# mw_itb_full_v1_7_2.net
KiCad netlist of a schematic drawn in EAGLE
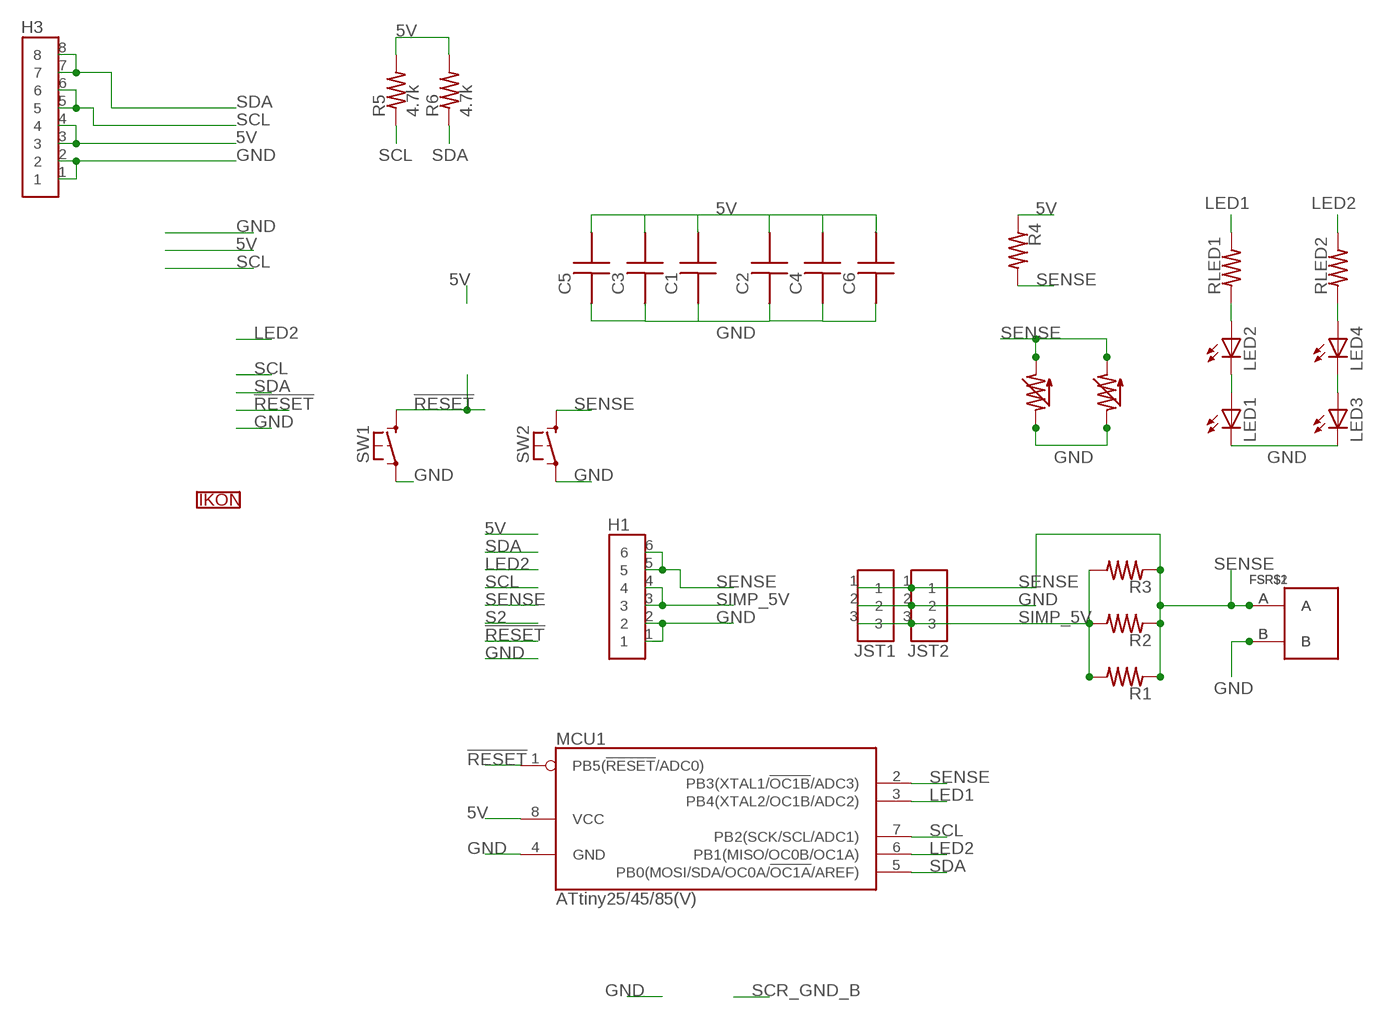
[diagram p0: schematic, sheet 1]

(export (version "E")
  (design (tool "Eeschema 10.0.6"))
  (components
    (comp (ref "C1")
      (value "CAPACITOR1206")
      (footprint "eagle-import:1206_YAGEO")
      (libsource (lib "eagle-import") (part "CAPACITOR1206"))
    )
    (comp (ref "C2")
      (value "CAPACITOR1206")
      (footprint "eagle-import:1206_YAGEO")
      (libsource (lib "eagle-import") (part "CAPACITOR1206"))
    )
    (comp (ref "C3")
      (value "CAPACITOR0805")
      (footprint "eagle-import:0805_YAGEO")
      (libsource (lib "eagle-import") (part "CAPACITOR0805"))
    )
    (comp (ref "C4")
      (value "CAPACITOR0805")
      (footprint "eagle-import:0805_YAGEO")
      (libsource (lib "eagle-import") (part "CAPACITOR0805"))
    )
    (comp (ref "C5")
      (value "CAPACITOR0603")
      (footprint "eagle-import:0603_YAGEO")
      (libsource (lib "eagle-import") (part "CAPACITOR0603"))
    )
    (comp (ref "C6")
      (value "CAPACITOR0603")
      (footprint "eagle-import:0603_YAGEO")
      (libsource (lib "eagle-import") (part "CAPACITOR0603"))
    )
    (comp (ref "FSR$1")
      (value "FSR_PAD88X44_P2B")
      (footprint "eagle-import:FSR_PAD_88X44_P2B")
      (libsource (lib "eagle-import") (part "FSR_PAD88X44_P2B"))
    )
    (comp (ref "FSR$2")
      (value "FSR_PAD88X44_P2B")
      (footprint "eagle-import:FSR_PAD_88X44_P2B")
      (libsource (lib "eagle-import") (part "FSR_PAD88X44_P2B"))
    )
    (comp (ref "H1")
      (value "HEADER_6P-0.1\"_2X3-SMD-SULLINS")
      (footprint "eagle-import:HEADER-0.1__2X3-SMD-SULLINS")
      (libsource (lib "eagle-import") (part "HEADER_6P-0.1{dblquote}_2X3-SMD-SULLINS"))
    )
    (comp (ref "H3")
      (value "HEADER_8P-0.1\"_2X4-SMD-SULLINS")
      (footprint "eagle-import:HEADER-0.1__2X4-SMD-SULLINS")
      (libsource (lib "eagle-import") (part "HEADER_8P-0.1{dblquote}_2X4-SMD-SULLINS"))
    )
    (comp (ref "JST1")
      (value "JST-3-PH-SMD-TOP")
      (footprint "eagle-import:JST_PH_SMD_3_TOP")
      (libsource (lib "eagle-import") (part "JST-3-PH-SMD-TOP"))
    )
    (comp (ref "JST2")
      (value "JST-3-PH-SMD-TOP")
      (footprint "eagle-import:JST_PH_SMD_3_TOP")
      (libsource (lib "eagle-import") (part "JST-3-PH-SMD-TOP"))
    )
    (comp (ref "LED1")
      (value "LED-ZBEND_RM")
      (footprint "eagle-import:Z-BEND_RM")
      (libsource (lib "eagle-import") (part "LED-ZBEND_RM"))
    )
    (comp (ref "LED2")
      (value "LED-ZBEND_RM")
      (footprint "eagle-import:Z-BEND_RM")
      (libsource (lib "eagle-import") (part "LED-ZBEND_RM"))
    )
    (comp (ref "LED3")
      (value "LED-ZBEND_RM")
      (footprint "eagle-import:Z-BEND_RM")
      (libsource (lib "eagle-import") (part "LED-ZBEND_RM"))
    )
    (comp (ref "LED4")
      (value "LED-ZBEND_RM")
      (footprint "eagle-import:Z-BEND_RM")
      (libsource (lib "eagle-import") (part "LED-ZBEND_RM"))
    )
    (comp (ref "MCU1")
      (value "ATMEL_ATTINY25/45/85(V)-SOIC_DUAL")
      (footprint "eagle-import:SOIC-8_DUAL")
      (libsource (lib "eagle-import") (part "ATMEL_ATTINY25/45/85(V)-SOIC_DUAL"))
    )
    (comp (ref "R1")
      (value "RESISTOR1206")
      (footprint "eagle-import:1206_YAGEO")
      (libsource (lib "eagle-import") (part "RESISTOR1206"))
    )
    (comp (ref "R2")
      (value "RESISTOR0805")
      (footprint "eagle-import:0805_YAGEO")
      (libsource (lib "eagle-import") (part "RESISTOR0805"))
    )
    (comp (ref "R3")
      (value "RESISTOR0603")
      (footprint "eagle-import:0603_YAGEO")
      (libsource (lib "eagle-import") (part "RESISTOR0603"))
    )
    (comp (ref "R4")
      (value "RESISTOR0603")
      (footprint "eagle-import:0603_YAGEO")
      (libsource (lib "eagle-import") (part "RESISTOR0603"))
    )
    (comp (ref "R5")
      (value "4.7k")
      (footprint "eagle-import:0603_YAGEO")
      (libsource (lib "eagle-import") (part "RESISTOR0603"))
    )
    (comp (ref "R6")
      (value "4.7k")
      (footprint "eagle-import:0603_YAGEO")
      (libsource (lib "eagle-import") (part "RESISTOR0603"))
    )
    (comp (ref "RLED1")
      (value "RESISTOR0603")
      (footprint "eagle-import:0603_YAGEO")
      (libsource (lib "eagle-import") (part "RESISTOR0603"))
    )
    (comp (ref "RLED2")
      (value "RESISTOR0603")
      (footprint "eagle-import:0603_YAGEO")
      (libsource (lib "eagle-import") (part "RESISTOR0603"))
    )
    (comp (ref "SW1")
      (value "SWITCH_SPST-KMT0")
      (footprint "eagle-import:KMT0")
      (libsource (lib "eagle-import") (part "SWITCH_SPST-KMT0"))
    )
    (comp (ref "SW2")
      (value "SWITCH_SPST-KMT0")
      (footprint "eagle-import:KMT0")
      (libsource (lib "eagle-import") (part "SWITCH_SPST-KMT0"))
    )
    (comp (ref "U$1")
      (value "FSR_PINS")
      (footprint "eagle-import:FSR_0.1_-PITCH_PADS-0.05_X0.5_")
      (libsource (lib "eagle-import") (part "FSR_PINSJUMBO_SMD"))
    )
    (comp (ref "U$2")
      (value "FSR_PLACE")
      (footprint "eagle-import:FSR_1.5[IN]_SQR")
      (libsource (lib "eagle-import") (part "FSR_PLACE1.5{dblquote}SQR"))
    )
    (comp (ref "U$3")
      (value "FSR_PINS")
      (footprint "eagle-import:FSR_0.1_-PITCH_PADS-0.05_X0.5_")
      (libsource (lib "eagle-import") (part "FSR_PINSJUMBO_SMD"))
    )
    (comp (ref "U$4")
      (value "FSR_PLACE")
      (footprint "eagle-import:FSR_1.5[IN]_SQR")
      (libsource (lib "eagle-import") (part "FSR_PLACE1.5{dblquote}SQR"))
    )
    (comp (ref "U$5")
      (value "FSR_PLACE")
      (footprint "eagle-import:FSR_1.5[IN]_SQR")
      (libsource (lib "eagle-import") (part "FSR_PLACE1.5{dblquote}SQR"))
    )
    (comp (ref "U$6")
      (value "FSR_PLACE")
      (footprint "eagle-import:FSR_1.5[IN]_SQR")
      (libsource (lib "eagle-import") (part "FSR_PLACE1.5{dblquote}SQR"))
    )
    (comp (ref "U$9")
      (value "FSR_PINS")
      (footprint "eagle-import:FSR_0.1_-PITCH_PADS-0.05_X0.5_")
      (libsource (lib "eagle-import") (part "FSR_PINSJUMBO_SMD"))
    )
    (comp (ref "U$10")
      (value "FSR_PINS")
      (footprint "eagle-import:FSR_0.1_-PITCH_PADS-0.05_X0.5_")
      (libsource (lib "eagle-import") (part "FSR_PINSJUMBO_SMD"))
    )
    (comp (ref "U$11")
      (value "IKONLEARNING-20MIL")
      (footprint "eagle-import:IKON_LEARNING_20MIL")
      (libsource (lib "eagle-import") (part "IKONLEARNING-20MIL"))
    )
  )
  (nets
    (net (code "1") (name "/5V") (class "Default")
      (node (ref "C1") (pin "1") (pinfunction "P$1_1") (pintype "passive"))
      (node (ref "C2") (pin "1") (pinfunction "P$1_1") (pintype "passive"))
      (node (ref "C3") (pin "1") (pinfunction "P$1_1") (pintype "passive"))
      (node (ref "C4") (pin "1") (pinfunction "P$1_1") (pintype "passive"))
      (node (ref "C5") (pin "1") (pinfunction "P$1_1") (pintype "passive"))
      (node (ref "C6") (pin "1") (pinfunction "P$1_1") (pintype "passive"))
      (node (ref "H3") (pin "3") (pinfunction "3_3") (pintype "bidirectional"))
      (node (ref "H3") (pin "4") (pinfunction "4_4") (pintype "bidirectional"))
      (node (ref "MCU1") (pin "8") (pinfunction "VCC_8") (pintype "bidirectional"))
      (node (ref "R4") (pin "1") (pinfunction "1_1") (pintype "passive"))
      (node (ref "R5") (pin "2") (pinfunction "2_2") (pintype "passive"))
      (node (ref "R6") (pin "2") (pinfunction "2_2") (pintype "passive"))
    )
    (net (code "2") (name "/GND") (class "Default")
      (node (ref "C1") (pin "2") (pinfunction "P$2_2") (pintype "passive"))
      (node (ref "C2") (pin "2") (pinfunction "P$2_2") (pintype "passive"))
      (node (ref "C3") (pin "2") (pinfunction "P$2_2") (pintype "passive"))
      (node (ref "C4") (pin "2") (pinfunction "P$2_2") (pintype "passive"))
      (node (ref "C5") (pin "2") (pinfunction "P$2_2") (pintype "passive"))
      (node (ref "C6") (pin "2") (pinfunction "P$2_2") (pintype "passive"))
      (node (ref "FSR$1") (pin "B") (pinfunction "B_B") (pintype "bidirectional"))
      (node (ref "FSR$2") (pin "B") (pinfunction "B_B") (pintype "bidirectional"))
      (node (ref "H1") (pin "1") (pinfunction "1_1") (pintype "bidirectional"))
      (node (ref "H1") (pin "2") (pinfunction "2_2") (pintype "bidirectional"))
      (node (ref "H3") (pin "1") (pinfunction "1_1") (pintype "bidirectional"))
      (node (ref "H3") (pin "2") (pinfunction "2_2") (pintype "bidirectional"))
      (node (ref "JST1") (pin "2") (pinfunction "2_2") (pintype "bidirectional"))
      (node (ref "JST2") (pin "2") (pinfunction "2_2") (pintype "bidirectional"))
      (node (ref "LED1") (pin "K") (pinfunction "C_K") (pintype "passive"))
      (node (ref "LED3") (pin "K") (pinfunction "C_K") (pintype "passive"))
      (node (ref "MCU1") (pin "4") (pinfunction "GND_4") (pintype "bidirectional"))
      (node (ref "SW1") (pin "2@1") (pinfunction "2_2@1") (pintype "passive"))
      (node (ref "SW1") (pin "2@2") (pinfunction "2_2@2") (pintype "passive"))
      (node (ref "SW2") (pin "2@1") (pinfunction "2_2@1") (pintype "passive"))
      (node (ref "SW2") (pin "2@2") (pinfunction "2_2@2") (pintype "passive"))
      (node (ref "U$1") (pin "P$1") (pinfunction "P$1_P$1") (pintype "bidirectional"))
      (node (ref "U$10") (pin "P$1") (pinfunction "P$1_P$1") (pintype "bidirectional"))
      (node (ref "U$3") (pin "P$2") (pinfunction "P$2_P$2") (pintype "bidirectional"))
      (node (ref "U$9") (pin "P$2") (pinfunction "P$2_P$2") (pintype "bidirectional"))
    )
    (net (code "3") (name "/LED1") (class "Default")
      (node (ref "MCU1") (pin "3") (pinfunction "PB4(XTAL2/OC1B/ADC2)_3") (pintype "bidirectional"))
      (node (ref "RLED1") (pin "2") (pinfunction "2_2") (pintype "passive"))
    )
    (net (code "4") (name "/LED2") (class "Default")
      (node (ref "MCU1") (pin "6") (pinfunction "PB1(MISO/OC0B/OC1A)_6") (pintype "bidirectional"))
      (node (ref "RLED2") (pin "2") (pinfunction "2_2") (pintype "passive"))
    )
    (net (code "6") (name "/SCL") (class "Default")
      (node (ref "H3") (pin "5") (pinfunction "5_5") (pintype "bidirectional"))
      (node (ref "H3") (pin "6") (pinfunction "6_6") (pintype "bidirectional"))
      (node (ref "MCU1") (pin "7") (pinfunction "PB2(SCK/SCL/ADC1)_7") (pintype "bidirectional"))
      (node (ref "R5") (pin "1") (pinfunction "1_1") (pintype "passive"))
    )
    (net (code "8") (name "/SDA") (class "Default")
      (node (ref "H3") (pin "7") (pinfunction "7_7") (pintype "bidirectional"))
      (node (ref "H3") (pin "8") (pinfunction "8_8") (pintype "bidirectional"))
      (node (ref "MCU1") (pin "5") (pinfunction "PB0(MOSI/SDA/OC0A/~{OC1A}/AREF)_5") (pintype "bidirectional"))
      (node (ref "R6") (pin "1") (pinfunction "1_1") (pintype "passive"))
    )
    (net (code "9") (name "/SENSE") (class "Default")
      (node (ref "FSR$1") (pin "A") (pinfunction "A_A") (pintype "bidirectional"))
      (node (ref "FSR$2") (pin "A") (pinfunction "A_A") (pintype "bidirectional"))
      (node (ref "H1") (pin "5") (pinfunction "5_5") (pintype "bidirectional"))
      (node (ref "H1") (pin "6") (pinfunction "6_6") (pintype "bidirectional"))
      (node (ref "JST1") (pin "1") (pinfunction "1_1") (pintype "bidirectional"))
      (node (ref "JST2") (pin "1") (pinfunction "1_1") (pintype "bidirectional"))
      (node (ref "MCU1") (pin "2") (pinfunction "PB3(XTAL1/~{OC1B}/ADC3)_2") (pintype "bidirectional"))
      (node (ref "R1") (pin "1") (pinfunction "1_1") (pintype "passive"))
      (node (ref "R2") (pin "1") (pinfunction "1_1") (pintype "passive"))
      (node (ref "R3") (pin "1") (pinfunction "1_1") (pintype "passive"))
      (node (ref "R4") (pin "2") (pinfunction "2_2") (pintype "passive"))
      (node (ref "SW2") (pin "1@1") (pinfunction "1_1@1") (pintype "passive"))
      (node (ref "SW2") (pin "1@2") (pinfunction "1_1@2") (pintype "passive"))
      (node (ref "U$1") (pin "P$2") (pinfunction "P$2_P$2") (pintype "bidirectional"))
      (node (ref "U$10") (pin "P$2") (pinfunction "P$2_P$2") (pintype "bidirectional"))
      (node (ref "U$3") (pin "P$1") (pinfunction "P$1_P$1") (pintype "bidirectional"))
      (node (ref "U$9") (pin "P$1") (pinfunction "P$1_P$1") (pintype "bidirectional"))
    )
    (net (code "10") (name "/SIMP_5V") (class "Default")
      (node (ref "H1") (pin "3") (pinfunction "3_3") (pintype "bidirectional"))
      (node (ref "H1") (pin "4") (pinfunction "4_4") (pintype "bidirectional"))
      (node (ref "JST1") (pin "3") (pinfunction "3_3") (pintype "bidirectional"))
      (node (ref "JST2") (pin "3") (pinfunction "3_3") (pintype "bidirectional"))
      (node (ref "R1") (pin "2") (pinfunction "2_2") (pintype "passive"))
      (node (ref "R2") (pin "2") (pinfunction "2_2") (pintype "passive"))
      (node (ref "R3") (pin "2") (pinfunction "2_2") (pintype "passive"))
    )
    (net (code "11") (name "/~{RESET}") (class "Default")
      (node (ref "MCU1") (pin "1") (pinfunction "PB5(~{RESET}/ADC0)_1") (pintype "bidirectional"))
      (node (ref "SW1") (pin "1@1") (pinfunction "1_1@1") (pintype "passive"))
      (node (ref "SW1") (pin "1@2") (pinfunction "1_1@2") (pintype "passive"))
    )
    (net (code "12") (name "Net-(LED2-C)") (class "Default")
      (node (ref "LED1") (pin "A") (pinfunction "A_A") (pintype "passive"))
      (node (ref "LED2") (pin "K") (pinfunction "C_K") (pintype "passive"))
    )
    (net (code "13") (name "Net-(LED2-PadA)") (class "Default")
      (node (ref "LED2") (pin "A") (pinfunction "A_A") (pintype "passive"))
      (node (ref "RLED1") (pin "1") (pinfunction "1_1") (pintype "passive"))
    )
    (net (code "14") (name "Net-(LED4-C)") (class "Default")
      (node (ref "LED3") (pin "A") (pinfunction "A_A") (pintype "passive"))
      (node (ref "LED4") (pin "K") (pinfunction "C_K") (pintype "passive"))
    )
    (net (code "15") (name "Net-(LED4-PadA)") (class "Default")
      (node (ref "LED4") (pin "A") (pinfunction "A_A") (pintype "passive"))
      (node (ref "RLED2") (pin "1") (pinfunction "1_1") (pintype "passive"))
    )
  )
)
